# vccs_pullup.net
KiCad netlist of a schematic drawn in Altium Designer
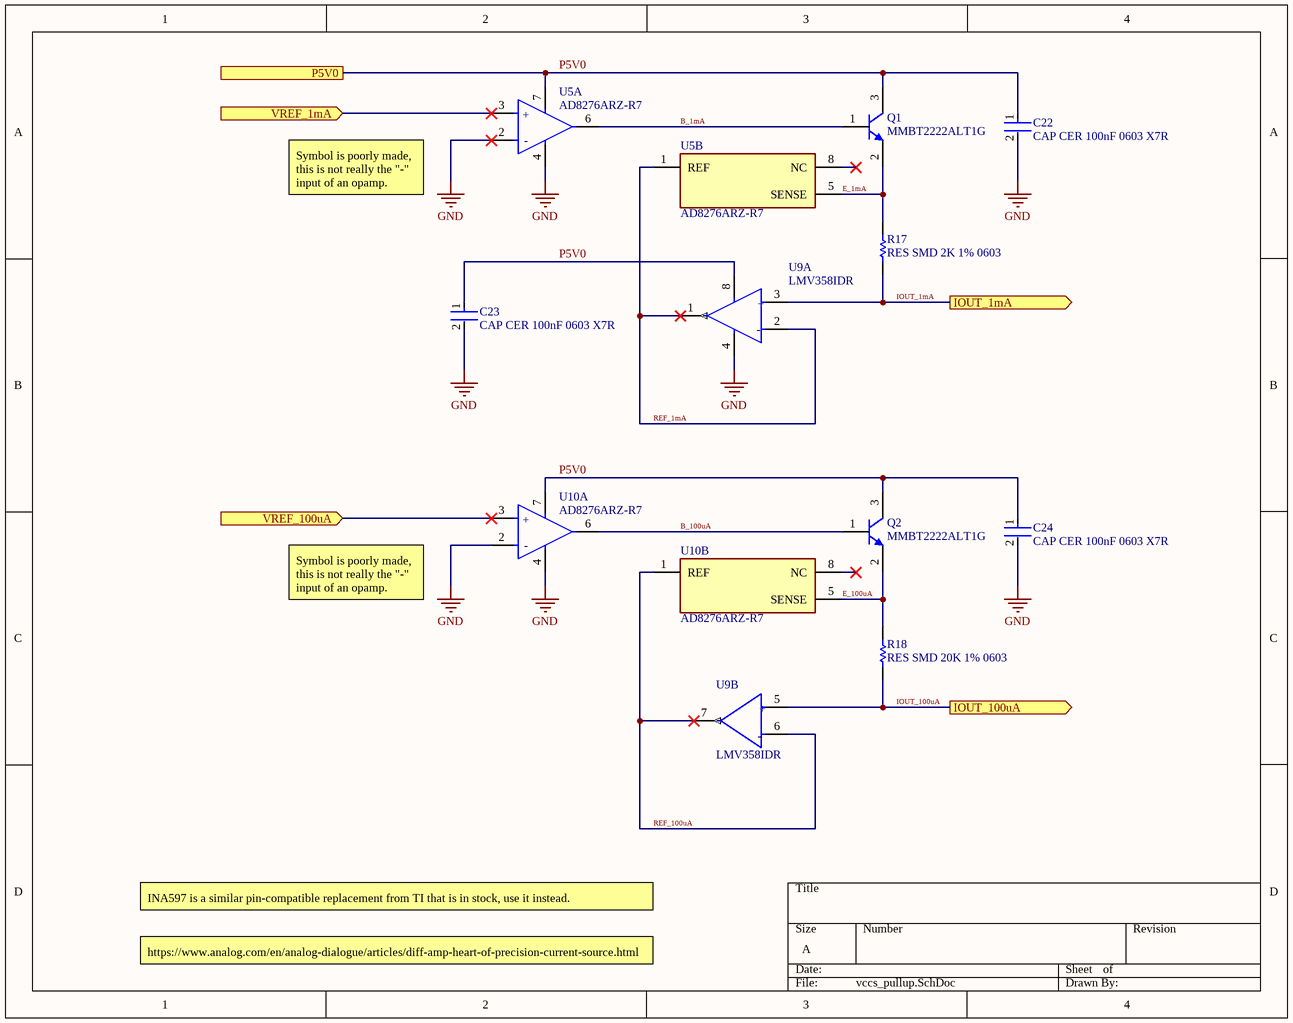
[diagram p0: vccs_pullup.SchDoc]

(export (version "E")
  (design (tool "Eeschema 10.0.6"))
  (components
    (comp (ref "C22")
      (value "CAP CER 100nF 0603 X7R")
      (footprint "FP-CC0603-DA-MFG")
      (description "CAP CER 0.1UF 16V X7R 0603")
      (fields
        (field (name "OCTOPART") "https://octopart.com/cc0603krx7r7bb104-yageo-192941")
        (field (name "TOLERANCE") "0.1")
      )
      (libsource (lib "Altium Content Vault") (part "11868f565c42a9108669ba33697ecf6"))
    )
    (comp (ref "C23")
      (value "CAP CER 100nF 0603 X7R")
      (footprint "FP-CC0603-DA-MFG")
      (description "CAP CER 0.1UF 16V X7R 0603")
      (fields
        (field (name "OCTOPART") "https://octopart.com/cc0603krx7r7bb104-yageo-192941")
        (field (name "TOLERANCE") "0.1")
      )
      (libsource (lib "Altium Content Vault") (part "11868f565c42a9108669ba33697ecf6"))
    )
    (comp (ref "C24")
      (value "CAP CER 100nF 0603 X7R")
      (footprint "FP-CC0603-DA-MFG")
      (description "CAP CER 0.1UF 16V X7R 0603")
      (fields
        (field (name "OCTOPART") "https://octopart.com/cc0603krx7r7bb104-yageo-192941")
        (field (name "TOLERANCE") "0.1")
      )
      (libsource (lib "Altium Content Vault") (part "11868f565c42a9108669ba33697ecf6"))
    )
    (comp (ref "Q1")
      (value "MMBT2222ALT1G")
      (footprint "ONSC-SOT-23-3-318-08_V")
      (description "General Purpose Transistor, NPN Silicon, 3-Pin SOT-23, Pb-Free, Tape and Reel")
      (fields (field (name "MANUFACTURER") "On Semiconductor"))
      (libsource (lib "Altium Content Vault") (part "ONSC-NPN-B1E2C3-3"))
    )
    (comp (ref "Q2")
      (value "MMBT2222ALT1G")
      (footprint "ONSC-SOT-23-3-318-08_V")
      (description "General Purpose Transistor, NPN Silicon, 3-Pin SOT-23, Pb-Free, Tape and Reel")
      (fields (field (name "MANUFACTURER") "On Semiconductor"))
      (libsource (lib "Altium Content Vault") (part "ONSC-NPN-B1E2C3-3"))
    )
    (comp (ref "R17")
      (value "RES SMD 2K 1% 0603")
      (footprint "RESC1609X50X30LL10T20")
      (description "DNP")
      (fields (field (name "PART NUMBER") "CRCW0603100KFKEA") (field (name "MANUFACTURER") "Vishay Dale"))
      (libsource (lib "Altium Content Vault") (part "RES"))
    )
    (comp (ref "R18")
      (value "RES SMD 20K 1% 0603")
      (footprint "RESC1609X50X30LL10T20")
      (description "DNP")
      (fields (field (name "PART NUMBER") "CRCW0603100KFKEA") (field (name "MANUFACTURER") "Vishay Dale"))
      (libsource (lib "Altium Content Vault") (part "RES"))
    )
    (comp (ref "U5")
      (value "AD8276ARZ-R7")
      (footprint "FP-R-8-IPC_C")
      (description "IC OPAMP DIFF 1 CIRCUIT 8SOIC")
      (libsource (lib "Altium Content Vault") (part "9c3c1701abf421b3e1a52f423b28bfa"))
    )
    (comp (ref "U9")
      (value "LMV358IDR")
      (footprint "FP-D0008A-MFG")
      (description "IC OPAMP GP 2 CIRCUIT 8SOIC")
      (libsource (lib "Altium Content Vault") (part "1f85fec4e6914445158f776dbf16c1d"))
    )
    (comp (ref "U10")
      (value "AD8276ARZ-R7")
      (footprint "FP-R-8-IPC_C")
      (description "IC OPAMP DIFF 1 CIRCUIT 8SOIC")
      (libsource (lib "Altium Content Vault") (part "9c3c1701abf421b3e1a52f423b28bfa"))
    )
  )
  (nets
    (net (code "1") (name "/B_1mA") (class "Default")
      (node (ref "Q1") (pin "1") (pinfunction "B_1") (pintype "passive"))
      (node (ref "U5") (pin "6") (pinfunction "OUT_6") (pintype "passive"))
    )
    (net (code "2") (name "/B_100uA") (class "Default")
      (node (ref "Q2") (pin "1") (pinfunction "B_1") (pintype "passive"))
      (node (ref "U10") (pin "6") (pinfunction "OUT_6") (pintype "passive"))
    )
    (net (code "3") (name "/E_1mA") (class "Default")
      (node (ref "Q1") (pin "2") (pinfunction "E_2") (pintype "passive"))
      (node (ref "R17") (pin "2") (pinfunction "2_2") (pintype "passive"))
      (node (ref "U5") (pin "5") (pinfunction "SENSE_5") (pintype "passive"))
    )
    (net (code "4") (name "/E_100uA") (class "Default")
      (node (ref "Q2") (pin "2") (pinfunction "E_2") (pintype "passive"))
      (node (ref "R18") (pin "2") (pinfunction "2_2") (pintype "passive"))
      (node (ref "U10") (pin "5") (pinfunction "SENSE_5") (pintype "passive"))
    )
    (net (code "5") (name "/IOUT_1mA") (class "Default")
      (node (ref "R17") (pin "1") (pinfunction "1_1") (pintype "passive"))
      (node (ref "U9") (pin "3") (pinfunction "1IN+_3") (pintype "tri_state"))
    )
    (net (code "6") (name "/IOUT_100uA") (class "Default")
      (node (ref "R18") (pin "1") (pinfunction "1_1") (pintype "passive"))
      (node (ref "U9") (pin "5") (pinfunction "2IN+_5") (pintype "tri_state"))
    )
    (net (code "7") (name "/P5V0") (class "Default")
      (node (ref "C22") (pin "1") (pinfunction "1_1") (pintype "passive"))
      (node (ref "C23") (pin "1") (pinfunction "1_1") (pintype "passive"))
      (node (ref "C24") (pin "1") (pinfunction "1_1") (pintype "passive"))
      (node (ref "Q1") (pin "3") (pinfunction "C_3") (pintype "passive"))
      (node (ref "Q2") (pin "3") (pinfunction "C_3") (pintype "passive"))
      (node (ref "U10") (pin "7") (pinfunction "+VS_7") (pintype "power_in"))
      (node (ref "U5") (pin "7") (pinfunction "+VS_7") (pintype "power_in"))
      (node (ref "U9") (pin "8") (pinfunction "VCC+_8") (pintype "power_in"))
    )
    (net (code "8") (name "/REF_1mA") (class "Default")
      (node (ref "U5") (pin "1") (pinfunction "REF_1") (pintype "passive"))
      (node (ref "U9") (pin "1") (pinfunction "OUT_1") (pintype "output"))
      (node (ref "U9") (pin "2") (pinfunction "1IN-_2") (pintype "tri_state"))
    )
    (net (code "9") (name "/REF_100uA") (class "Default")
      (node (ref "U10") (pin "1") (pinfunction "REF_1") (pintype "passive"))
      (node (ref "U9") (pin "6") (pinfunction "2IN-_6") (pintype "tri_state"))
      (node (ref "U9") (pin "7") (pinfunction "2OUT_7") (pintype "output"))
    )
    (net (code "10") (name "/VREF_1mA") (class "Default")
      (node (ref "U5") (pin "3") (pinfunction "+IN_3") (pintype "tri_state+no_connect"))
    )
    (net (code "11") (name "/VREF_100uA") (class "Default")
      (node (ref "U10") (pin "3") (pinfunction "+IN_3") (pintype "tri_state+no_connect"))
    )
    (net (code "12") (name "GND") (class "Default")
      (node (ref "C22") (pin "2") (pinfunction "2_2") (pintype "passive"))
      (node (ref "C23") (pin "2") (pinfunction "2_2") (pintype "passive"))
      (node (ref "C24") (pin "2") (pinfunction "2_2") (pintype "passive"))
      (node (ref "U10") (pin "2") (pinfunction "-IN_2") (pintype "tri_state"))
      (node (ref "U10") (pin "4") (pinfunction "-VS_4") (pintype "power_in"))
      (node (ref "U5") (pin "2") (pinfunction "-IN_2") (pintype "tri_state"))
      (node (ref "U5") (pin "4") (pinfunction "-VS_4") (pintype "power_in"))
      (node (ref "U9") (pin "4") (pinfunction "GND_4") (pintype "power_in"))
    )
    (net (code "13") (name "unconnected-(U5B-NC-Pad8)") (class "Default")
      (node (ref "U5") (pin "8") (pinfunction "NC_8") (pintype "passive+no_connect"))
    )
    (net (code "14") (name "unconnected-(U10B-NC-Pad8)") (class "Default")
      (node (ref "U10") (pin "8") (pinfunction "NC_8") (pintype "passive+no_connect"))
    )
  )
)
